# power_output_SCH3.net
KiCad netlist of a schematic drawn in Altium Designer
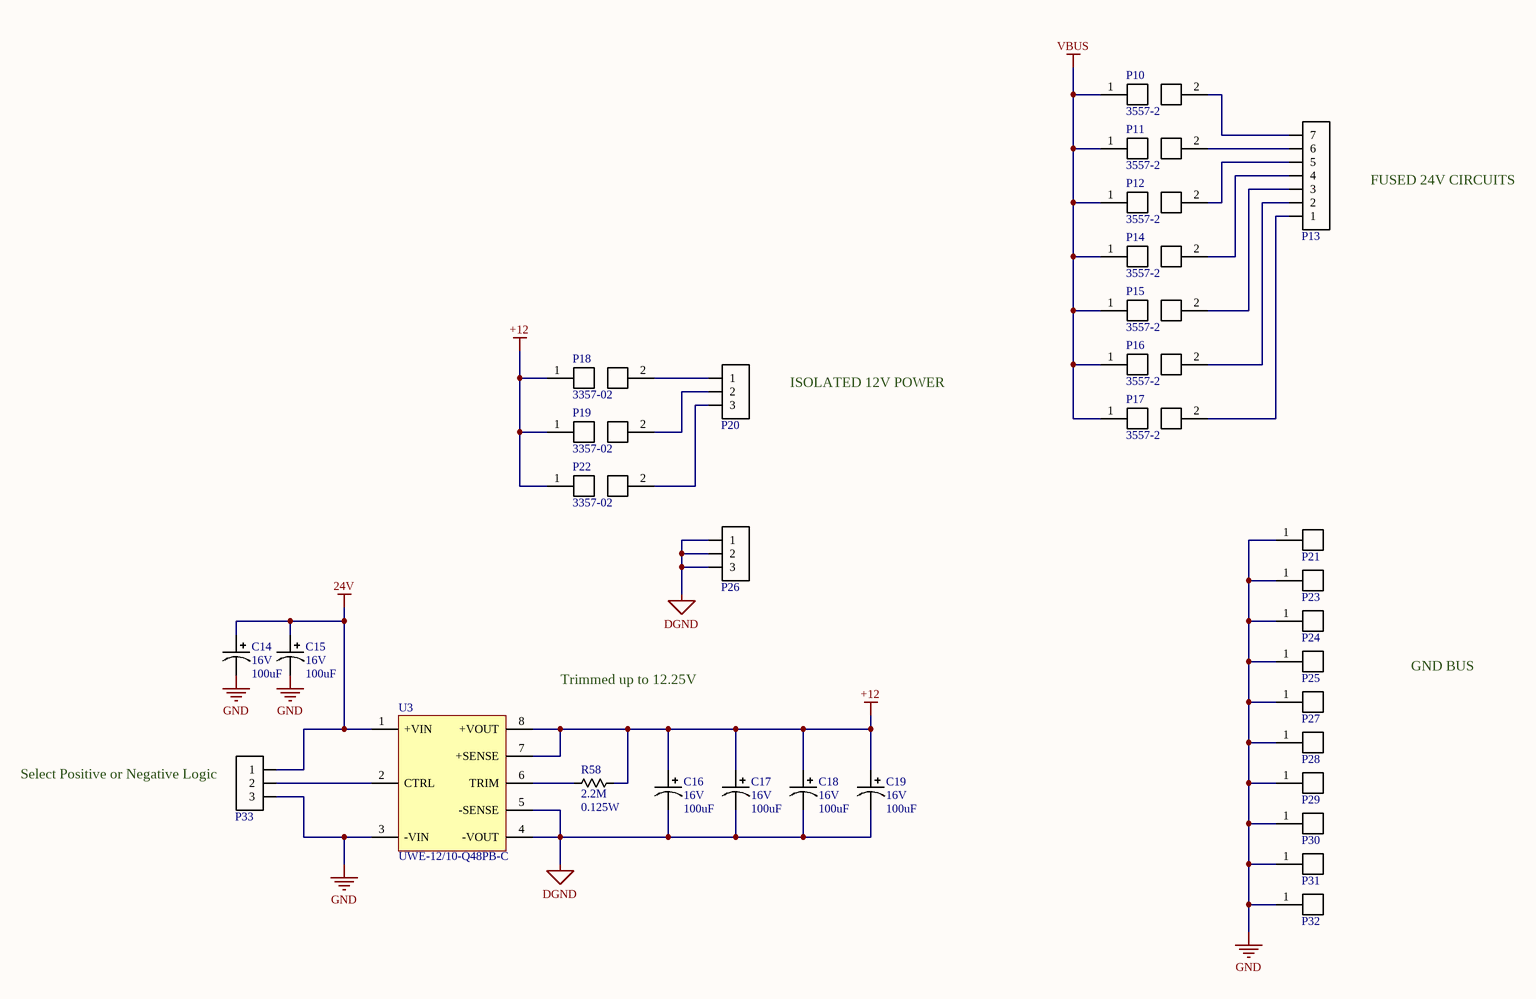
[diagram p0: power_output_SCH3.SchDoc]

(export (version "E")
  (design (tool "Eeschema 10.0.6"))
  (components
    (comp (ref "C14")
      (value "cap_single_p")
      (footprint "chip_2917_AVX_TAJD")
      (description "CAP, 100uF, ±10%, 16V, Tantalum, 2917")
      (fields
        (field (name "TOLERANCE") "±10%")
        (field (name "VOLTAGE RATING") "16V")
        (field (name "CAPACITANCE") "100uF")
        (field (name "PART NUMBER") "CAP-00550")
      )
      (libsource (lib "Capacitors") (part "cap_single_p"))
    )
    (comp (ref "C15")
      (value "cap_single_p")
      (footprint "chip_2917_AVX_TAJD")
      (description "CAP, 100uF, ±10%, 16V, Tantalum, 2917")
      (fields
        (field (name "TOLERANCE") "±10%")
        (field (name "VOLTAGE RATING") "16V")
        (field (name "CAPACITANCE") "100uF")
        (field (name "PART NUMBER") "CAP-00550")
      )
      (libsource (lib "Capacitors") (part "cap_single_p"))
    )
    (comp (ref "C16")
      (value "cap_single_p")
      (footprint "chip_2917_AVX_TAJD")
      (description "CAP, 100uF, ±10%, 16V, Tantalum, 2917")
      (fields
        (field (name "TOLERANCE") "±10%")
        (field (name "VOLTAGE RATING") "16V")
        (field (name "CAPACITANCE") "100uF")
        (field (name "PART NUMBER") "CAP-00550")
      )
      (libsource (lib "Capacitors") (part "cap_single_p"))
    )
    (comp (ref "C17")
      (value "cap_single_p")
      (footprint "chip_2917_AVX_TAJD")
      (description "CAP, 100uF, ±10%, 16V, Tantalum, 2917")
      (fields
        (field (name "TOLERANCE") "±10%")
        (field (name "VOLTAGE RATING") "16V")
        (field (name "CAPACITANCE") "100uF")
        (field (name "PART NUMBER") "CAP-00550")
      )
      (libsource (lib "Capacitors") (part "cap_single_p"))
    )
    (comp (ref "C18")
      (value "cap_single_p")
      (footprint "chip_2917_AVX_TAJD")
      (description "CAP, 100uF, ±10%, 16V, Tantalum, 2917")
      (fields
        (field (name "TOLERANCE") "±10%")
        (field (name "VOLTAGE RATING") "16V")
        (field (name "CAPACITANCE") "100uF")
        (field (name "PART NUMBER") "CAP-00550")
      )
      (libsource (lib "Capacitors") (part "cap_single_p"))
    )
    (comp (ref "C19")
      (value "cap_single_p")
      (footprint "chip_2917_AVX_TAJD")
      (description "CAP, 100uF, ±10%, 16V, Tantalum, 2917")
      (fields
        (field (name "TOLERANCE") "±10%")
        (field (name "VOLTAGE RATING") "16V")
        (field (name "CAPACITANCE") "100uF")
        (field (name "PART NUMBER") "CAP-00550")
      )
      (libsource (lib "Capacitors") (part "cap_single_p"))
    )
    (comp (ref "P10")
      (value "conn-fuse-holder_0")
      (footprint "FUSE_HOLDER_KEYSTONE_3557-2")
      (description "Fuse Holder, 30A, 500V, LP-Mini 897, ATOF 257")
      (fields
        (field (name "MANUFACTURER PN") "3557-2")
        (field (name "PART NUMBER") "CONN-00015")
        (field (name "MANUFACTURER") "Keystone Electronics")
      )
      (libsource (lib "Connectors") (part "conn-fuse-holder_0"))
    )
    (comp (ref "P11")
      (value "conn-fuse-holder_0")
      (footprint "FUSE_HOLDER_KEYSTONE_3557-2")
      (description "Fuse Holder, 30A, 500V, LP-Mini 897, ATOF 257")
      (fields
        (field (name "MANUFACTURER PN") "3557-2")
        (field (name "PART NUMBER") "CONN-00015")
        (field (name "MANUFACTURER") "Keystone Electronics")
      )
      (libsource (lib "Connectors") (part "conn-fuse-holder_0"))
    )
    (comp (ref "P12")
      (value "conn-fuse-holder_0")
      (footprint "FUSE_HOLDER_KEYSTONE_3557-2")
      (description "Fuse Holder, 30A, 500V, LP-Mini 897, ATOF 257")
      (fields
        (field (name "MANUFACTURER PN") "3557-2")
        (field (name "PART NUMBER") "CONN-00015")
        (field (name "MANUFACTURER") "Keystone Electronics")
      )
      (libsource (lib "Connectors") (part "conn-fuse-holder_0"))
    )
    (comp (ref "P13")
      (value "conn-7x1_0")
      (footprint "MOLEX_387207507")
      (description "Barrier Blk, 7 Pos, 25A, 300V, 0.375\" pitch")
      (fields (field (name "PART NUMBER") "CONN-00051") (field (name "MANUFACTURER") "Molex"))
      (libsource (lib "Connectors") (part "conn-7x1_0"))
    )
    (comp (ref "P14")
      (value "conn-fuse-holder_0")
      (footprint "FUSE_HOLDER_KEYSTONE_3557-2")
      (description "Fuse Holder, 30A, 500V, LP-Mini 897, ATOF 257")
      (fields
        (field (name "MANUFACTURER PN") "3557-2")
        (field (name "PART NUMBER") "CONN-00015")
        (field (name "MANUFACTURER") "Keystone Electronics")
      )
      (libsource (lib "Connectors") (part "conn-fuse-holder_0"))
    )
    (comp (ref "P15")
      (value "conn-fuse-holder_0")
      (footprint "FUSE_HOLDER_KEYSTONE_3557-2")
      (description "Fuse Holder, 30A, 500V, LP-Mini 897, ATOF 257")
      (fields
        (field (name "MANUFACTURER PN") "3557-2")
        (field (name "PART NUMBER") "CONN-00015")
        (field (name "MANUFACTURER") "Keystone Electronics")
      )
      (libsource (lib "Connectors") (part "conn-fuse-holder_0"))
    )
    (comp (ref "P16")
      (value "conn-fuse-holder_0")
      (footprint "FUSE_HOLDER_KEYSTONE_3557-2")
      (description "Fuse Holder, 30A, 500V, LP-Mini 897, ATOF 257")
      (fields
        (field (name "MANUFACTURER PN") "3557-2")
        (field (name "PART NUMBER") "CONN-00015")
        (field (name "MANUFACTURER") "Keystone Electronics")
      )
      (libsource (lib "Connectors") (part "conn-fuse-holder_0"))
    )
    (comp (ref "P17")
      (value "conn-fuse-holder_0")
      (footprint "FUSE_HOLDER_KEYSTONE_3557-2")
      (description "Fuse Holder, 30A, 500V, LP-Mini 897, ATOF 257")
      (fields
        (field (name "MANUFACTURER PN") "3557-2")
        (field (name "PART NUMBER") "CONN-00015")
        (field (name "MANUFACTURER") "Keystone Electronics")
      )
      (libsource (lib "Connectors") (part "conn-fuse-holder_0"))
    )
    (comp (ref "P18")
      (value "conn-fuse-holder_0")
      (footprint "FUSE_HOLDER_KEYSTONE_3557-2")
      (description "Fuse Holder, 30A, 500V, LP-Mini 897, ATOF 257")
      (fields
        (field (name "MANUFACTURER PN") "3357-02")
        (field (name "PART NUMBER") "CONN-00015")
        (field (name "MANUFACTURER") "Keystone Electronics")
      )
      (libsource (lib "Connectors") (part "conn-fuse-holder_0"))
    )
    (comp (ref "P19")
      (value "conn-fuse-holder_0")
      (footprint "FUSE_HOLDER_KEYSTONE_3557-2")
      (description "Fuse Holder, 30A, 500V, LP-Mini 897, ATOF 257")
      (fields
        (field (name "MANUFACTURER PN") "3357-02")
        (field (name "PART NUMBER") "CONN-00015")
        (field (name "MANUFACTURER") "Keystone Electronics")
      )
      (libsource (lib "Connectors") (part "conn-fuse-holder_0"))
    )
    (comp (ref "P20")
      (value "conn-3x1_0")
      (footprint "PHOENIX_MKDS_5.08MM_3x1")
      (description "Term Blk, 3 Pos, 0.2\", 10A, 14-30 AWG, Rising Cage Clamp")
      (fields (field (name "PART NUMBER") "CONN-00021") (field (name "MANUFACTURER") "Phoenix Contact"))
      (libsource (lib "Connectors") (part "conn-3x1_0"))
    )
    (comp (ref "P21")
      (value "conn-1x1_0")
      (footprint "KEYSTONE_7798")
      (description "Screw Terminal, M4, 30A")
      (fields (field (name "PART NUMBER") "CONN-00042") (field (name "MANUFACTURER") "Keystone"))
      (libsource (lib "Connectors") (part "conn-1x1_0"))
    )
    (comp (ref "P22")
      (value "conn-fuse-holder_0")
      (footprint "FUSE_HOLDER_KEYSTONE_3557-2")
      (description "Fuse Holder, 30A, 500V, LP-Mini 897, ATOF 257")
      (fields
        (field (name "MANUFACTURER PN") "3357-02")
        (field (name "PART NUMBER") "CONN-00015")
        (field (name "MANUFACTURER") "Keystone Electronics")
      )
      (libsource (lib "Connectors") (part "conn-fuse-holder_0"))
    )
    (comp (ref "P23")
      (value "conn-1x1_0")
      (footprint "KEYSTONE_7798")
      (description "Screw Terminal, M4, 30A")
      (fields (field (name "PART NUMBER") "CONN-00042") (field (name "MANUFACTURER") "Keystone"))
      (libsource (lib "Connectors") (part "conn-1x1_0"))
    )
    (comp (ref "P24")
      (value "conn-1x1_0")
      (footprint "KEYSTONE_7798")
      (description "Screw Terminal, M4, 30A")
      (fields (field (name "PART NUMBER") "CONN-00042") (field (name "MANUFACTURER") "Keystone"))
      (libsource (lib "Connectors") (part "conn-1x1_0"))
    )
    (comp (ref "P25")
      (value "conn-1x1_0")
      (footprint "KEYSTONE_7798")
      (description "Screw Terminal, M4, 30A")
      (fields (field (name "PART NUMBER") "CONN-00042") (field (name "MANUFACTURER") "Keystone"))
      (libsource (lib "Connectors") (part "conn-1x1_0"))
    )
    (comp (ref "P26")
      (value "conn-3x1_0")
      (footprint "PHOENIX_MKDS_5.08MM_3x1")
      (description "Term Blk, 3 Pos, 0.2\", 10A, 14-30 AWG, Rising Cage Clamp")
      (fields (field (name "PART NUMBER") "CONN-00021") (field (name "MANUFACTURER") "Phoenix Contact"))
      (libsource (lib "Connectors") (part "conn-3x1_0"))
    )
    (comp (ref "P27")
      (value "conn-1x1_0")
      (footprint "KEYSTONE_7798")
      (description "Screw Terminal, M4, 30A")
      (fields (field (name "PART NUMBER") "CONN-00042") (field (name "MANUFACTURER") "Keystone"))
      (libsource (lib "Connectors") (part "conn-1x1_0"))
    )
    (comp (ref "P28")
      (value "conn-1x1_0")
      (footprint "KEYSTONE_7798")
      (description "Screw Terminal, M4, 30A")
      (fields (field (name "PART NUMBER") "CONN-00042") (field (name "MANUFACTURER") "Keystone"))
      (libsource (lib "Connectors") (part "conn-1x1_0"))
    )
    (comp (ref "P29")
      (value "conn-1x1_0")
      (footprint "KEYSTONE_7798")
      (description "Screw Terminal, M4, 30A")
      (fields (field (name "PART NUMBER") "CONN-00042") (field (name "MANUFACTURER") "Keystone"))
      (libsource (lib "Connectors") (part "conn-1x1_0"))
    )
    (comp (ref "P30")
      (value "conn-1x1_0")
      (footprint "KEYSTONE_7798")
      (description "Screw Terminal, M4, 30A")
      (fields (field (name "PART NUMBER") "CONN-00042") (field (name "MANUFACTURER") "Keystone"))
      (libsource (lib "Connectors") (part "conn-1x1_0"))
    )
    (comp (ref "P31")
      (value "conn-1x1_0")
      (footprint "KEYSTONE_7798")
      (description "Screw Terminal, M4, 30A")
      (fields (field (name "PART NUMBER") "CONN-00042") (field (name "MANUFACTURER") "Keystone"))
      (libsource (lib "Connectors") (part "conn-1x1_0"))
    )
    (comp (ref "P32")
      (value "conn-1x1_0")
      (footprint "KEYSTONE_7798")
      (description "Screw Terminal, M4, 30A")
      (fields (field (name "PART NUMBER") "CONN-00042") (field (name "MANUFACTURER") "Keystone"))
      (libsource (lib "Connectors") (part "conn-1x1_0"))
    )
    (comp (ref "P33")
      (value "conn-3x1_0")
      (footprint "hddr_3x1_0")
      (description "Header, 3x1, 0.1\"")
      (fields (field (name "PART NUMBER") "CONN-00037"))
      (libsource (lib "Connectors") (part "conn-3x1_0"))
    )
    (comp (ref "R58")
      (value "res_single")
      (footprint "chip_0805")
      (description "RES SMD 2.2M OHM 1% 1/8W 0805")
      (fields
        (field (name "TOLERANCE") "1%")
        (field (name "RESISTANCE") "2.2M")
        (field (name "POWER RATING") "0.125W")
        (field (name "PART NUMBER") "RES-00367")
      )
      (libsource (lib "Resistors") (part "res_single"))
    )
    (comp (ref "U3")
      (value "eighth_brick_module_8")
      (footprint "EIGHTH_BRICK_6_0")
      (description "Module, Isolated, Eighth-Brick, 12V, 10A, Positive Logic")
      (fields
        (field (name "MANUFACTURER PN") "UWE-12/10-Q48PB-C")
        (field (name "PART NUMBER") "PWREG-00026")
        (field (name "MANUFACTURER") "Murata")
      )
      (libsource (lib "Power Reg") (part "eighth_brick_module_8"))
    )
  )
  (nets
    (net (code "1") (name "+12") (class "Default")
      (node (ref "C16") (pin "1") (pinfunction "1_1") (pintype "passive"))
      (node (ref "C17") (pin "1") (pinfunction "1_1") (pintype "passive"))
      (node (ref "C18") (pin "1") (pinfunction "1_1") (pintype "passive"))
      (node (ref "C19") (pin "1") (pinfunction "1_1") (pintype "passive"))
      (node (ref "P18") (pin "1") (pinfunction "1_1") (pintype "passive"))
      (node (ref "P19") (pin "1") (pinfunction "1_1") (pintype "passive"))
      (node (ref "P22") (pin "1") (pinfunction "1_1") (pintype "passive"))
      (node (ref "R58") (pin "2") (pinfunction "2_2") (pintype "passive"))
      (node (ref "U3") (pin "7") (pinfunction "+SENSE_7") (pintype "passive"))
      (node (ref "U3") (pin "8") (pinfunction "+VOUT_8") (pintype "passive"))
    )
    (net (code "2") (name "24V") (class "Default")
      (node (ref "C14") (pin "1") (pinfunction "1_1") (pintype "passive"))
      (node (ref "C15") (pin "1") (pinfunction "1_1") (pintype "passive"))
      (node (ref "P33") (pin "1") (pinfunction "1_1") (pintype "passive"))
      (node (ref "U3") (pin "1") (pinfunction "+VIN_1") (pintype "passive"))
    )
    (net (code "3") (name "DGND") (class "Default")
      (node (ref "C16") (pin "2") (pinfunction "2_2") (pintype "passive"))
      (node (ref "C17") (pin "2") (pinfunction "2_2") (pintype "passive"))
      (node (ref "C18") (pin "2") (pinfunction "2_2") (pintype "passive"))
      (node (ref "C19") (pin "2") (pinfunction "2_2") (pintype "passive"))
      (node (ref "P26") (pin "1") (pinfunction "1_1") (pintype "passive"))
      (node (ref "P26") (pin "2") (pinfunction "2_2") (pintype "passive"))
      (node (ref "P26") (pin "3") (pinfunction "3_3") (pintype "passive"))
      (node (ref "U3") (pin "4") (pinfunction "-VOUT_4") (pintype "passive"))
      (node (ref "U3") (pin "5") (pinfunction "-SENSE_5") (pintype "passive"))
    )
    (net (code "4") (name "GND") (class "Default")
      (node (ref "C14") (pin "2") (pinfunction "2_2") (pintype "passive"))
      (node (ref "C15") (pin "2") (pinfunction "2_2") (pintype "passive"))
      (node (ref "P21") (pin "1") (pinfunction "P_1") (pintype "passive"))
      (node (ref "P23") (pin "1") (pinfunction "P_1") (pintype "passive"))
      (node (ref "P24") (pin "1") (pinfunction "P_1") (pintype "passive"))
      (node (ref "P25") (pin "1") (pinfunction "P_1") (pintype "passive"))
      (node (ref "P27") (pin "1") (pinfunction "P_1") (pintype "passive"))
      (node (ref "P28") (pin "1") (pinfunction "P_1") (pintype "passive"))
      (node (ref "P29") (pin "1") (pinfunction "P_1") (pintype "passive"))
      (node (ref "P30") (pin "1") (pinfunction "P_1") (pintype "passive"))
      (node (ref "P31") (pin "1") (pinfunction "P_1") (pintype "passive"))
      (node (ref "P32") (pin "1") (pinfunction "P_1") (pintype "passive"))
      (node (ref "P33") (pin "3") (pinfunction "3_3") (pintype "passive"))
      (node (ref "U3") (pin "3") (pinfunction "-VIN_3") (pintype "passive"))
    )
    (net (code "5") (name "Net-(P10-Pad2)") (class "Default")
      (node (ref "P10") (pin "2") (pinfunction "2_2") (pintype "passive"))
      (node (ref "P13") (pin "7") (pinfunction "7_7") (pintype "passive"))
    )
    (net (code "6") (name "Net-(P11-Pad2)") (class "Default")
      (node (ref "P11") (pin "2") (pinfunction "2_2") (pintype "passive"))
      (node (ref "P13") (pin "6") (pinfunction "6_6") (pintype "passive"))
    )
    (net (code "7") (name "Net-(P12-Pad2)") (class "Default")
      (node (ref "P12") (pin "2") (pinfunction "2_2") (pintype "passive"))
      (node (ref "P13") (pin "5") (pinfunction "5_5") (pintype "passive"))
    )
    (net (code "8") (name "Net-(P13-Pad1)") (class "Default")
      (node (ref "P13") (pin "1") (pinfunction "1_1") (pintype "passive"))
      (node (ref "P17") (pin "2") (pinfunction "2_2") (pintype "passive"))
    )
    (net (code "9") (name "Net-(P13-Pad2)") (class "Default")
      (node (ref "P13") (pin "2") (pinfunction "2_2") (pintype "passive"))
      (node (ref "P16") (pin "2") (pinfunction "2_2") (pintype "passive"))
    )
    (net (code "10") (name "Net-(P13-Pad3)") (class "Default")
      (node (ref "P13") (pin "3") (pinfunction "3_3") (pintype "passive"))
      (node (ref "P15") (pin "2") (pinfunction "2_2") (pintype "passive"))
    )
    (net (code "11") (name "Net-(P13-Pad4)") (class "Default")
      (node (ref "P13") (pin "4") (pinfunction "4_4") (pintype "passive"))
      (node (ref "P14") (pin "2") (pinfunction "2_2") (pintype "passive"))
    )
    (net (code "12") (name "Net-(P18-Pad2)") (class "Default")
      (node (ref "P18") (pin "2") (pinfunction "2_2") (pintype "passive"))
      (node (ref "P20") (pin "1") (pinfunction "1_1") (pintype "passive"))
    )
    (net (code "13") (name "Net-(P19-Pad2)") (class "Default")
      (node (ref "P19") (pin "2") (pinfunction "2_2") (pintype "passive"))
      (node (ref "P20") (pin "2") (pinfunction "2_2") (pintype "passive"))
    )
    (net (code "14") (name "Net-(P20-Pad3)") (class "Default")
      (node (ref "P20") (pin "3") (pinfunction "3_3") (pintype "passive"))
      (node (ref "P22") (pin "2") (pinfunction "2_2") (pintype "passive"))
    )
    (net (code "15") (name "Net-(U3-CTRL)") (class "Default")
      (node (ref "P33") (pin "2") (pinfunction "2_2") (pintype "passive"))
      (node (ref "U3") (pin "2") (pinfunction "CTRL_2") (pintype "passive"))
    )
    (net (code "16") (name "Net-(U3-TRIM)") (class "Default")
      (node (ref "R58") (pin "1") (pinfunction "1_1") (pintype "passive"))
      (node (ref "U3") (pin "6") (pinfunction "TRIM_6") (pintype "passive"))
    )
    (net (code "17") (name "VBUS") (class "Default")
      (node (ref "P10") (pin "1") (pinfunction "1_1") (pintype "passive"))
      (node (ref "P11") (pin "1") (pinfunction "1_1") (pintype "passive"))
      (node (ref "P12") (pin "1") (pinfunction "1_1") (pintype "passive"))
      (node (ref "P14") (pin "1") (pinfunction "1_1") (pintype "passive"))
      (node (ref "P15") (pin "1") (pinfunction "1_1") (pintype "passive"))
      (node (ref "P16") (pin "1") (pinfunction "1_1") (pintype "passive"))
      (node (ref "P17") (pin "1") (pinfunction "1_1") (pintype "passive"))
    )
  )
)
